# analog_heteroThermistor_1xChannel_R3.net
KiCad netlist of a schematic drawn in EAGLE
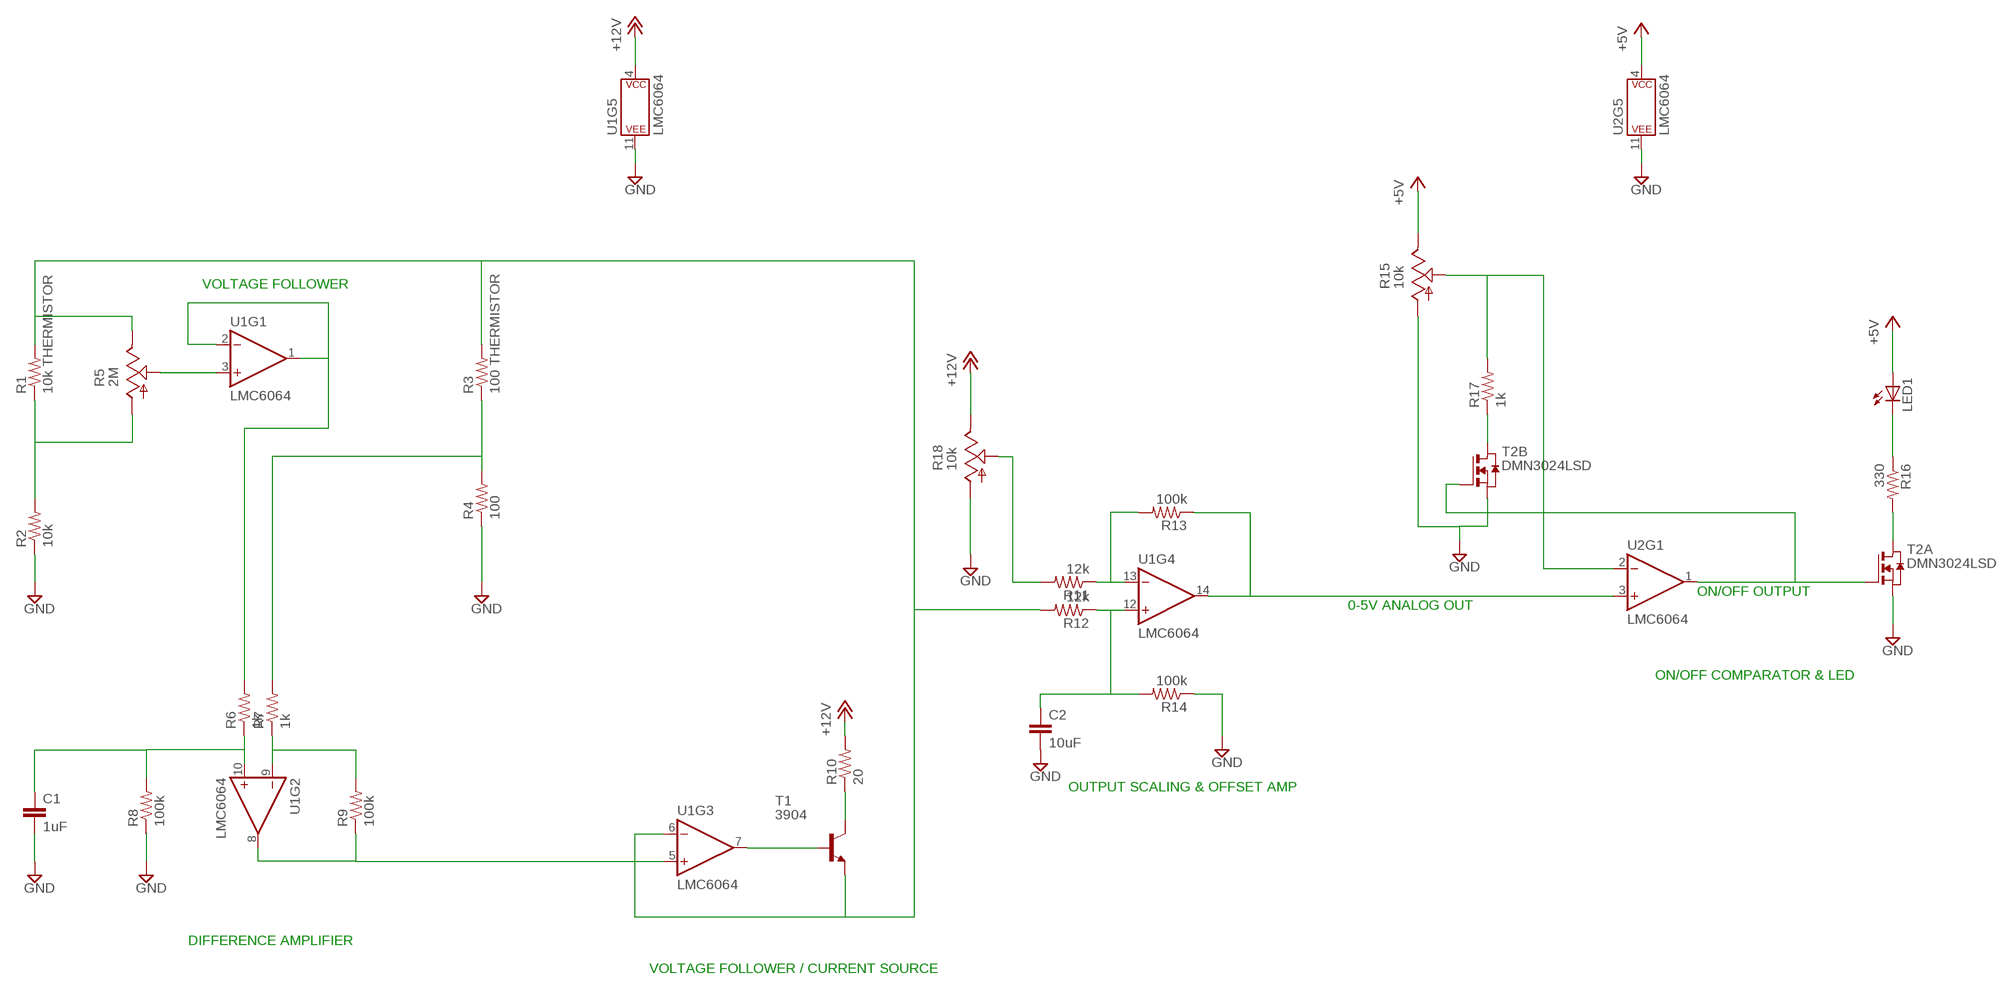
[diagram p0: schematic, sheet 1]

(export (version "E")
  (design (tool "Eeschema 10.0.6"))
  (components
    (comp (ref "C1")
      (value "1uF")
      (footprint "eagle-import:C0603")
      (fields
        (field (name "MF") "Murata Electronics North America")
        (field (name "MPN") "GRM188R61C105KA93D")
      )
      (libsource (lib "eagle-import") (part "C-EUC0603"))
    )
    (comp (ref "C2")
      (value "10uF")
      (footprint "eagle-import:C0603")
      (fields
        (field (name "MF") "Murata Electronics North America")
        (field (name "MPN") "GRM188C81C106MA73D")
      )
      (libsource (lib "eagle-import") (part "C-EUC0603"))
    )
    (comp (ref "LED1")
      (value "LEDCHIPLED_1206")
      (footprint "eagle-import:CHIPLED_1206")
      (fields (field (name "MF") "Lite-On Inc.") (field (name "MPN") "LTST-C150GKT"))
      (libsource (lib "eagle-import") (part "LEDCHIPLED_1206"))
    )
    (comp (ref "R1")
      (value "10k THERMISTOR")
      (footprint "eagle-import:R0603")
      (fields
        (field (name "DISTR") "Digikey")
        (field (name "DISTRPN") "490-2436-1-ND")
        (field (name "MF") "Murata Electronics North America")
        (field (name "MPN") "NCP18XH103J03RB")
      )
      (libsource (lib "eagle-import") (part "R-US_R0603"))
    )
    (comp (ref "R2")
      (value "10k")
      (footprint "eagle-import:R0603")
      (fields (field (name "MF") "Panasonic Electronic Components") (field (name "MPN") "ERJ-PA3F1002V"))
      (libsource (lib "eagle-import") (part "R-US_R0603"))
    )
    (comp (ref "R3")
      (value "100 THERMISTOR")
      (footprint "eagle-import:R0603")
      (fields
        (field (name "DISTR") "Digikey")
        (field (name "DISTRPN") "490-2434-1-ND")
        (field (name "MF") "Murata Electronics North America")
        (field (name "MPN") "NCP18XF101J03RB")
      )
      (libsource (lib "eagle-import") (part "R-US_R0603"))
    )
    (comp (ref "R4")
      (value "100")
      (footprint "eagle-import:R0603")
      (fields (field (name "MF") "Panasonic Electronic Components") (field (name "MPN") "ERJ-PA3F1000V"))
      (libsource (lib "eagle-import") (part "R-US_R0603"))
    )
    (comp (ref "R5")
      (value "2M")
      (footprint "eagle-import:SM-42_43W")
      (fields (field (name "MF") "Copal Electronics Inc.") (field (name "MPN") "SM-42TW205"))
      (libsource (lib "eagle-import") (part "TRIM_US-SM-42/43W"))
    )
    (comp (ref "R6")
      (value "1k")
      (footprint "eagle-import:R0603")
      (fields (field (name "MF") "Panasonic Electronic Components") (field (name "MPN") "ERJ-PA3F1001V"))
      (libsource (lib "eagle-import") (part "R-US_R0603"))
    )
    (comp (ref "R7")
      (value "1k")
      (footprint "eagle-import:R0603")
      (fields (field (name "MF") "Panasonic Electronic Components") (field (name "MPN") "ERJ-PA3F1001V"))
      (libsource (lib "eagle-import") (part "R-US_R0603"))
    )
    (comp (ref "R8")
      (value "100k")
      (footprint "eagle-import:R0603")
      (fields (field (name "MF") "Panasonic Electronic Components") (field (name "MPN") "ERJ-PA3F1003V"))
      (libsource (lib "eagle-import") (part "R-US_R0603"))
    )
    (comp (ref "R9")
      (value "100k")
      (footprint "eagle-import:R0603")
      (fields (field (name "MF") "Panasonic Electronic Components") (field (name "MPN") "ERJ-PA3F1003V"))
      (libsource (lib "eagle-import") (part "R-US_R0603"))
    )
    (comp (ref "R10")
      (value "20")
      (footprint "eagle-import:R0603")
      (fields (field (name "MF") "Panasonic Electronic Components") (field (name "MPN") "ERJ-PA3F20R0V"))
      (libsource (lib "eagle-import") (part "R-US_R0603"))
    )
    (comp (ref "R11")
      (value "12k")
      (footprint "eagle-import:R0603")
      (fields (field (name "MF") "Panasonic Electronic Components") (field (name "MPN") "ERJ-PA3F1202V"))
      (libsource (lib "eagle-import") (part "R-US_R0603"))
    )
    (comp (ref "R12")
      (value "12k")
      (footprint "eagle-import:R0603")
      (fields (field (name "MF") "Panasonic Electronic Components") (field (name "MPN") "ERJ-PA3F1202V"))
      (libsource (lib "eagle-import") (part "R-US_R0603"))
    )
    (comp (ref "R13")
      (value "100k")
      (footprint "eagle-import:R0603")
      (fields (field (name "MF") "Panasonic Electronic Components") (field (name "MPN") "ERJ-PA3F1003V"))
      (libsource (lib "eagle-import") (part "R-US_R0603"))
    )
    (comp (ref "R14")
      (value "100k")
      (footprint "eagle-import:R0603")
      (fields (field (name "MF") "Panasonic Electronic Components") (field (name "MPN") "ERJ-PA3F1003V"))
      (libsource (lib "eagle-import") (part "R-US_R0603"))
    )
    (comp (ref "R15")
      (value "10k")
      (footprint "eagle-import:SM-42_43W")
      (fields (field (name "MF") "Copal Electronics Inc.") (field (name "MPN") "SM-42TW103"))
      (libsource (lib "eagle-import") (part "TRIM_US-SM-42/43W"))
    )
    (comp (ref "R16")
      (value "330")
      (footprint "eagle-import:R0603")
      (fields (field (name "MF") "Panasonic Electronic Components") (field (name "MPN") "ERJ-PA3F3300V"))
      (libsource (lib "eagle-import") (part "R-US_R0603"))
    )
    (comp (ref "R17")
      (value "1k")
      (footprint "eagle-import:R0603")
      (fields (field (name "MF") "Panasonic Electronic Components") (field (name "MPN") "ERJ-PA3F1001V"))
      (libsource (lib "eagle-import") (part "R-US_R0603"))
    )
    (comp (ref "R18")
      (value "10k")
      (footprint "eagle-import:SM-42_43W")
      (fields (field (name "MF") "Copal Electronics Inc.") (field (name "MPN") "SM-42TW103"))
      (libsource (lib "eagle-import") (part "TRIM_US-SM-42/43W"))
    )
    (comp (ref "T1")
      (value "3904")
      (footprint "eagle-import:SOT23-BEC")
      (fields (field (name "MF") "Fairchild/ON Semiconductor") (field (name "MPN") "MMBT3904"))
      (libsource (lib "eagle-import") (part "-NPN-SOT23-BECMMBT3904LT1"))
    )
    (comp (ref "T2")
      (value "DMN3024LSD")
      (footprint "eagle-import:SO8")
      (fields
        (field (name "MF") "Diodes Incorporated")
        (field (name "MPN") "DMN3024LSD-13")
        (field (name "DISTR") "Digikey")
        (field (name "DISTRPN") "DMN3024LSD-13DICT-ND")
      )
      (libsource (lib "eagle-import") (part "DMN3024LSD"))
    )
    (comp (ref "U1")
      (value "LMC6064")
      (footprint "eagle-import:SO14")
      (fields
        (field (name "DISTR") "Digikey")
        (field (name "DISTRPN") "296-35438-1-ND")
        (field (name "MF") "Texas Instruments")
        (field (name "MPN") "LMC6064AIMX/NOPB")
      )
      (libsource (lib "eagle-import") (part "LMC6064"))
    )
    (comp (ref "U2")
      (value "LMC6064")
      (footprint "eagle-import:SO14")
      (fields
        (field (name "MF") "Texas Instruments")
        (field (name "MPN") "LMC6064AIMX/NOPB")
        (field (name "DISTR") "Digikey")
        (field (name "DISTRPN") "296-35438-1-ND")
      )
      (libsource (lib "eagle-import") (part "LMC6064"))
    )
  )
  (nets
    (net (code "1") (name "+5V") (class "Default")
      (node (ref "LED1") (pin "A") (pinfunction "A_A") (pintype "passive"))
      (node (ref "R15") (pin "3") (pinfunction "E_3") (pintype "passive"))
      (node (ref "U2") (pin "4") (pinfunction "P$V+_4") (pintype "bidirectional"))
    )
    (net (code "2") (name "+12V") (class "Default")
      (node (ref "R10") (pin "2") (pinfunction "2_2") (pintype "passive"))
      (node (ref "R18") (pin "3") (pinfunction "E_3") (pintype "passive"))
      (node (ref "U1") (pin "4") (pinfunction "P$V+_4") (pintype "bidirectional"))
    )
    (net (code "3") (name "GND") (class "Default")
      (node (ref "C1") (pin "2") (pinfunction "2_2") (pintype "passive"))
      (node (ref "C2") (pin "2") (pinfunction "2_2") (pintype "passive"))
      (node (ref "R14") (pin "1") (pinfunction "1_1") (pintype "passive"))
      (node (ref "R15") (pin "1") (pinfunction "A_1") (pintype "passive"))
      (node (ref "R18") (pin "1") (pinfunction "A_1") (pintype "passive"))
      (node (ref "R2") (pin "1") (pinfunction "1_1") (pintype "passive"))
      (node (ref "R4") (pin "1") (pinfunction "1_1") (pintype "passive"))
      (node (ref "R8") (pin "1") (pinfunction "1_1") (pintype "passive"))
      (node (ref "T2") (pin "1") (pinfunction "S_1") (pintype "passive"))
      (node (ref "T2") (pin "3") (pinfunction "S_3") (pintype "passive"))
      (node (ref "U1") (pin "11") (pinfunction "P$V-_11") (pintype "bidirectional"))
      (node (ref "U2") (pin "11") (pinfunction "P$V-_11") (pintype "bidirectional"))
    )
    (net (code "4") (name "Net-(LED1-PadC)") (class "Default")
      (node (ref "LED1") (pin "C") (pinfunction "C_C") (pintype "passive"))
      (node (ref "R16") (pin "1") (pinfunction "1_1") (pintype "passive"))
    )
    (net (code "5") (name "Net-(R3-Pad1)") (class "Default")
      (node (ref "R3") (pin "1") (pinfunction "1_1") (pintype "passive"))
      (node (ref "R4") (pin "2") (pinfunction "2_2") (pintype "passive"))
      (node (ref "R7") (pin "2") (pinfunction "2_2") (pintype "passive"))
    )
    (net (code "6") (name "Net-(R5-A)") (class "Default")
      (node (ref "R1") (pin "1") (pinfunction "1_1") (pintype "passive"))
      (node (ref "R2") (pin "2") (pinfunction "2_2") (pintype "passive"))
      (node (ref "R5") (pin "1") (pinfunction "A_1") (pintype "passive"))
    )
    (net (code "7") (name "Net-(R5-E)") (class "Default")
      (node (ref "R1") (pin "2") (pinfunction "2_2") (pintype "passive"))
      (node (ref "R12") (pin "2") (pinfunction "2_2") (pintype "passive"))
      (node (ref "R3") (pin "2") (pinfunction "2_2") (pintype "passive"))
      (node (ref "R5") (pin "3") (pinfunction "E_3") (pintype "passive"))
      (node (ref "T1") (pin "E") (pinfunction "E_E") (pintype "passive"))
      (node (ref "U1") (pin "6") (pinfunction "-IN_6") (pintype "input"))
    )
    (net (code "8") (name "Net-(R5-S)") (class "Default")
      (node (ref "R5") (pin "2") (pinfunction "S_2") (pintype "passive"))
      (node (ref "U1") (pin "3") (pinfunction "+IN_3") (pintype "input"))
    )
    (net (code "9") (name "Net-(R10-Pad1)") (class "Default")
      (node (ref "R10") (pin "1") (pinfunction "1_1") (pintype "passive"))
      (node (ref "T1") (pin "C") (pinfunction "C_C") (pintype "passive"))
    )
    (net (code "10") (name "Net-(R15-S)") (class "Default")
      (node (ref "R15") (pin "2") (pinfunction "S_2") (pintype "passive"))
      (node (ref "R17") (pin "2") (pinfunction "2_2") (pintype "passive"))
      (node (ref "U2") (pin "2") (pinfunction "-IN_2") (pintype "input"))
    )
    (net (code "11") (name "Net-(R16-Pad2)") (class "Default")
      (node (ref "R16") (pin "2") (pinfunction "2_2") (pintype "passive"))
      (node (ref "T2") (pin "7") (pinfunction "D_7") (pintype "passive"))
      (node (ref "T2") (pin "8") (pinfunction "D_8") (pintype "passive"))
    )
    (net (code "12") (name "Net-(R17-Pad1)") (class "Default")
      (node (ref "R17") (pin "1") (pinfunction "1_1") (pintype "passive"))
      (node (ref "T2") (pin "5") (pinfunction "D_5") (pintype "passive"))
      (node (ref "T2") (pin "6") (pinfunction "D_6") (pintype "passive"))
    )
    (net (code "13") (name "Net-(R18-S)") (class "Default")
      (node (ref "R11") (pin "2") (pinfunction "2_2") (pintype "passive"))
      (node (ref "R18") (pin "2") (pinfunction "S_2") (pintype "passive"))
    )
    (net (code "14") (name "Net-(T2A-G)") (class "Default")
      (node (ref "T2") (pin "2") (pinfunction "G_2") (pintype "passive"))
      (node (ref "T2") (pin "4") (pinfunction "G_4") (pintype "passive"))
      (node (ref "U2") (pin "1") (pinfunction "OUT_1") (pintype "output"))
    )
    (net (code "15") (name "Net-(U1A--IN)") (class "Default")
      (node (ref "R6") (pin "2") (pinfunction "2_2") (pintype "passive"))
      (node (ref "U1") (pin "1") (pinfunction "OUT_1") (pintype "output"))
      (node (ref "U1") (pin "2") (pinfunction "-IN_2") (pintype "input"))
    )
    (net (code "16") (name "Net-(U1B-+IN)") (class "Default")
      (node (ref "C1") (pin "1") (pinfunction "1_1") (pintype "passive"))
      (node (ref "R6") (pin "1") (pinfunction "1_1") (pintype "passive"))
      (node (ref "R8") (pin "2") (pinfunction "2_2") (pintype "passive"))
      (node (ref "U1") (pin "10") (pinfunction "+IN_10") (pintype "input"))
    )
    (net (code "17") (name "Net-(U1B--IN)") (class "Default")
      (node (ref "R7") (pin "1") (pinfunction "1_1") (pintype "passive"))
      (node (ref "R9") (pin "2") (pinfunction "2_2") (pintype "passive"))
      (node (ref "U1") (pin "9") (pinfunction "-IN_9") (pintype "input"))
    )
    (net (code "18") (name "Net-(U1B-OUT)") (class "Default")
      (node (ref "R9") (pin "1") (pinfunction "1_1") (pintype "passive"))
      (node (ref "U1") (pin "5") (pinfunction "+IN_5") (pintype "input"))
      (node (ref "U1") (pin "8") (pinfunction "OUT_8") (pintype "output"))
    )
    (net (code "19") (name "Net-(U1C-OUT)") (class "Default")
      (node (ref "T1") (pin "B") (pinfunction "B_B") (pintype "passive"))
      (node (ref "U1") (pin "7") (pinfunction "OUT_7") (pintype "output"))
    )
    (net (code "20") (name "Net-(U1D-+IN)") (class "Default")
      (node (ref "C2") (pin "1") (pinfunction "1_1") (pintype "passive"))
      (node (ref "R12") (pin "1") (pinfunction "1_1") (pintype "passive"))
      (node (ref "R14") (pin "2") (pinfunction "2_2") (pintype "passive"))
      (node (ref "U1") (pin "12") (pinfunction "+IN_12") (pintype "input"))
    )
    (net (code "21") (name "Net-(U1D--IN)") (class "Default")
      (node (ref "R11") (pin "1") (pinfunction "1_1") (pintype "passive"))
      (node (ref "R13") (pin "2") (pinfunction "2_2") (pintype "passive"))
      (node (ref "U1") (pin "13") (pinfunction "-IN_13") (pintype "input"))
    )
    (net (code "22") (name "Net-(U1D-OUT)") (class "Default")
      (node (ref "R13") (pin "1") (pinfunction "1_1") (pintype "passive"))
      (node (ref "U1") (pin "14") (pinfunction "OUT_14") (pintype "output"))
      (node (ref "U2") (pin "3") (pinfunction "+IN_3") (pintype "input"))
    )
  )
)
